# uLipo.net
KiCad netlist of a schematic drawn in EAGLE
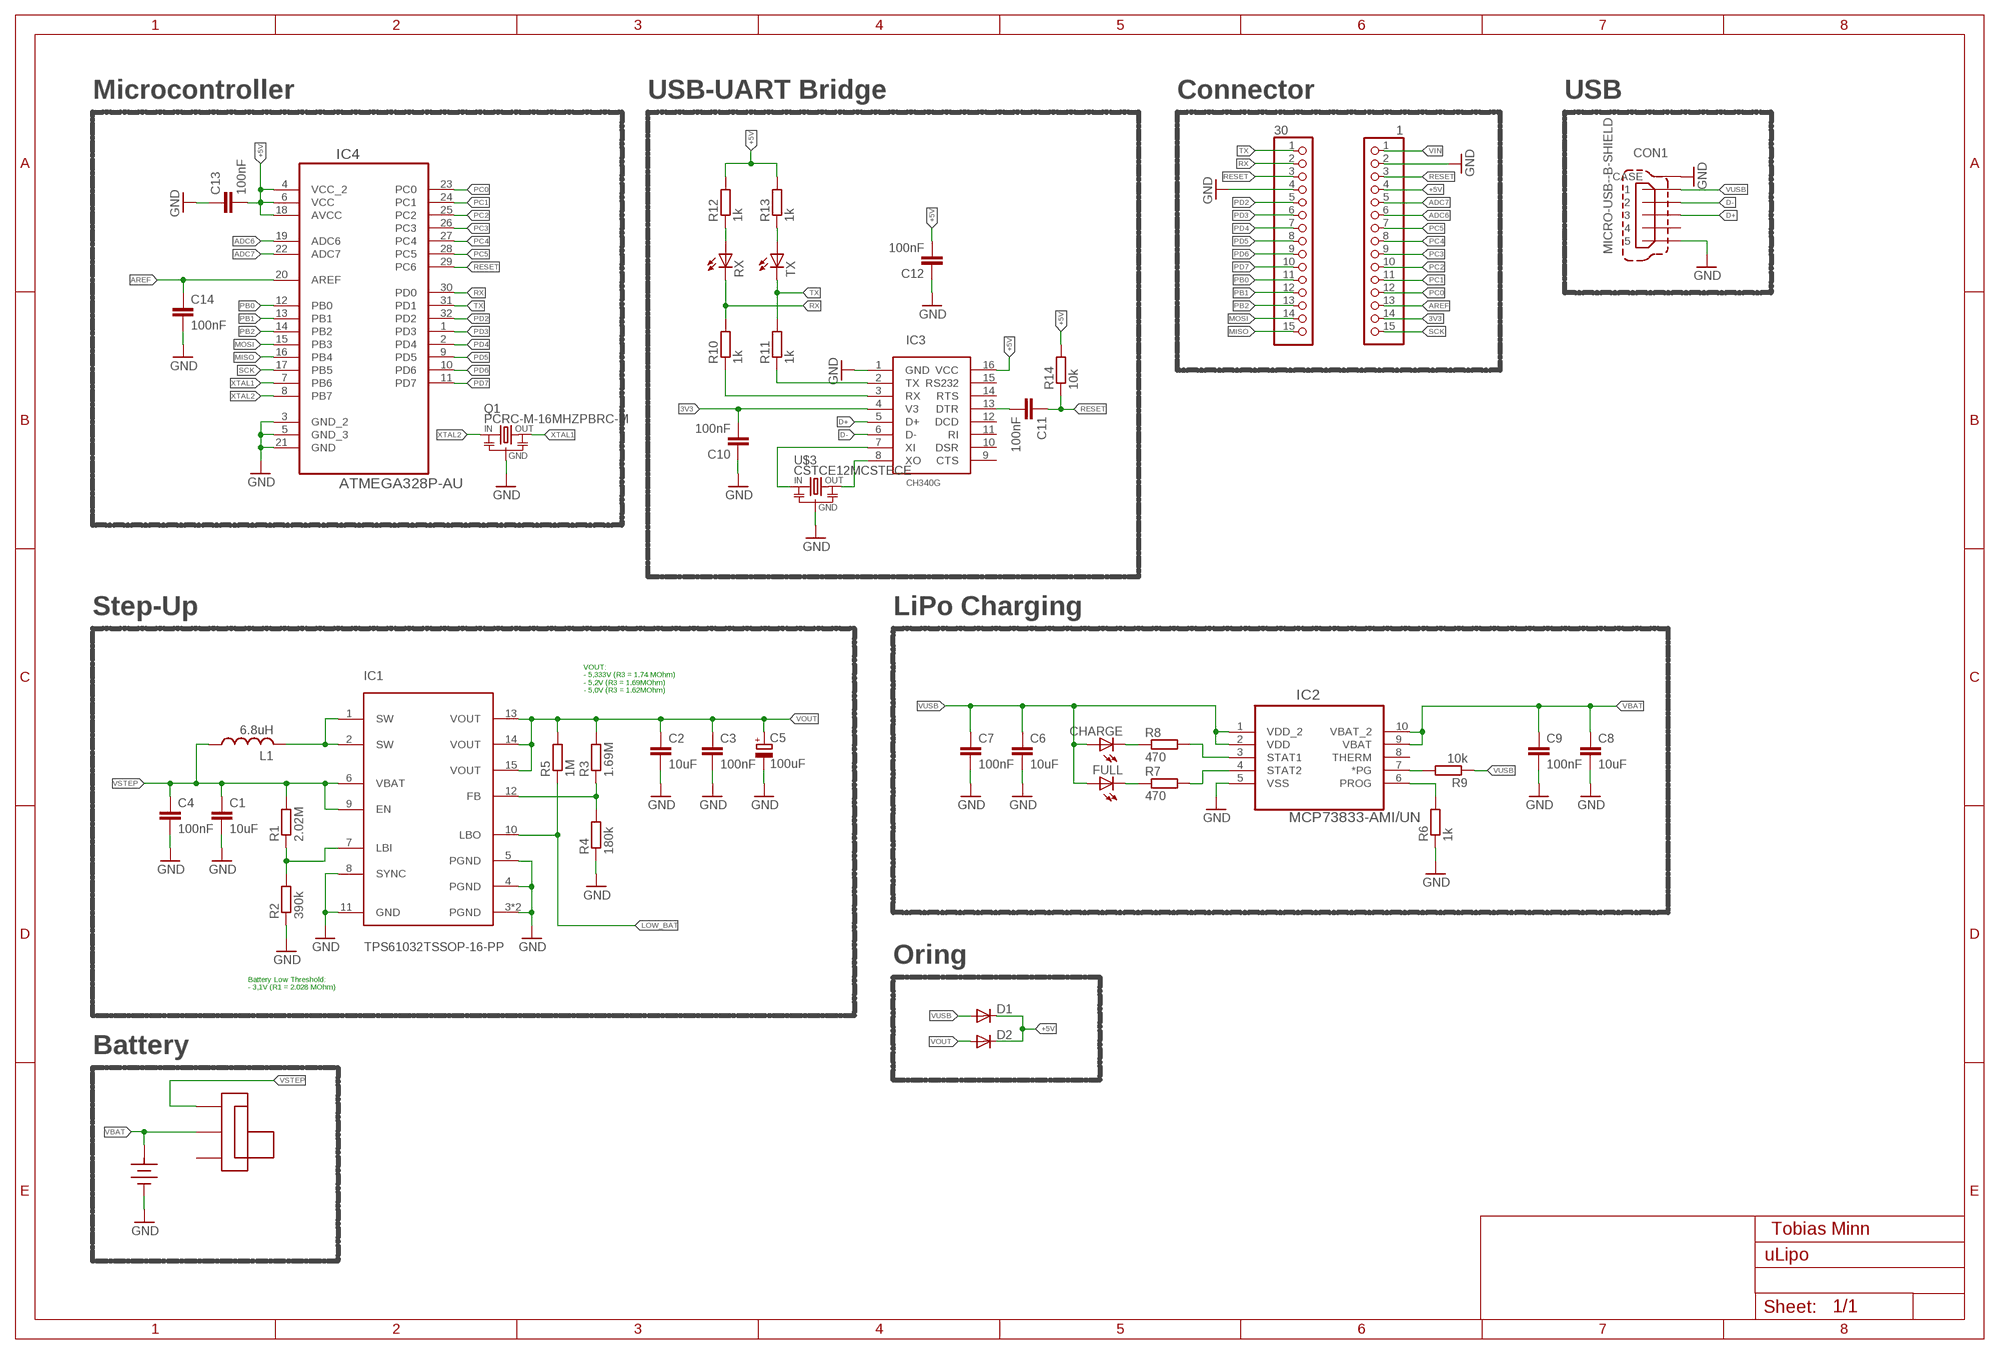
[diagram p0: schematic, sheet 1]

(export (version "E")
  (design (tool "Eeschema 10.0.6"))
  (components
    (comp (ref "1")
      (value "PINHD-1X15/OCT/BIG")
      (footprint "eagle-import:1X15_OCT_BIG")
      (libsource (lib "eagle-import") (part "PINHD-1X15/OCT/BIG"))
    )
    (comp (ref "30")
      (value "PINHD-1X15/OCT/BIG")
      (footprint "eagle-import:1X15_OCT_BIG")
      (libsource (lib "eagle-import") (part "PINHD-1X15/OCT/BIG"))
    )
    (comp (ref "BAT")
      (value "18650BATTERY")
      (footprint "eagle-import:18650BATTERY")
      (libsource (lib "eagle-import") (part "18650BATTERY"))
    )
    (comp (ref "C1")
      (value "10uF")
      (footprint "eagle-import:C0603K")
      (libsource (lib "eagle-import") (part "C-EUC0603K"))
    )
    (comp (ref "C2")
      (value "10uF")
      (footprint "eagle-import:C0603K")
      (libsource (lib "eagle-import") (part "C-EUC0603K"))
    )
    (comp (ref "C3")
      (value "100nF")
      (footprint "eagle-import:C0603K")
      (libsource (lib "eagle-import") (part "C-EUC0603K"))
    )
    (comp (ref "C4")
      (value "100nF")
      (footprint "eagle-import:C0603K")
      (libsource (lib "eagle-import") (part "C-EUC0603K"))
    )
    (comp (ref "C5")
      (value "100uF")
      (footprint "eagle-import:CT3528")
      (libsource (lib "eagle-import") (part "CPOL-EUCT3528"))
    )
    (comp (ref "C6")
      (value "10uF")
      (footprint "eagle-import:C0603K")
      (libsource (lib "eagle-import") (part "C-EUC0603K"))
    )
    (comp (ref "C7")
      (value "100nF")
      (footprint "eagle-import:C0603K")
      (libsource (lib "eagle-import") (part "C-EUC0603K"))
    )
    (comp (ref "C8")
      (value "10uF")
      (footprint "eagle-import:C0603K")
      (libsource (lib "eagle-import") (part "C-EUC0603K"))
    )
    (comp (ref "C9")
      (value "100nF")
      (footprint "eagle-import:C0603K")
      (libsource (lib "eagle-import") (part "C-EUC0603K"))
    )
    (comp (ref "C10")
      (value "100nF")
      (footprint "eagle-import:C0603K")
      (libsource (lib "eagle-import") (part "C-EUC0603K"))
    )
    (comp (ref "C11")
      (value "100nF")
      (footprint "eagle-import:C0603K")
      (libsource (lib "eagle-import") (part "C-EUC0603K"))
    )
    (comp (ref "C12")
      (value "100nF")
      (footprint "eagle-import:C0603K")
      (libsource (lib "eagle-import") (part "C-EUC0603K"))
    )
    (comp (ref "C13")
      (value "100nF")
      (footprint "eagle-import:C0603K")
      (libsource (lib "eagle-import") (part "C-EUC0603K"))
    )
    (comp (ref "C14")
      (value "100nF")
      (footprint "eagle-import:C0603K")
      (libsource (lib "eagle-import") (part "C-EUC0603K"))
    )
    (comp (ref "CHARGE")
      (value "LEDSML0603")
      (footprint "eagle-import:SML0603")
      (libsource (lib "eagle-import") (part "LEDSML0603"))
    )
    (comp (ref "CON1")
      (value "MICRO-USB--B-SHIELD")
      (footprint "eagle-import:MOLEX_47346-0001")
      (libsource (lib "eagle-import") (part "MICRO-USB--B-SHIELD"))
    )
    (comp (ref "D1")
      (value "DIODE-SOD123")
      (footprint "eagle-import:SOD123")
      (libsource (lib "eagle-import") (part "DIODE-SOD123"))
    )
    (comp (ref "D2")
      (value "DIODE-SOD123")
      (footprint "eagle-import:SOD123")
      (libsource (lib "eagle-import") (part "DIODE-SOD123"))
    )
    (comp (ref "FULL")
      (value "LEDSML0603")
      (footprint "eagle-import:SML0603")
      (libsource (lib "eagle-import") (part "LEDSML0603"))
    )
    (comp (ref "IC1")
      (value "TPS61032TSSOP-16-PP")
      (footprint "eagle-import:TSSOP-16-PP")
      (libsource (lib "eagle-import") (part "TPS61032TSSOP-16-PP"))
    )
    (comp (ref "IC2")
      (value "MCP73833-AMI/UN")
      (footprint "eagle-import:SOP50P490X110-10N")
      (libsource (lib "eagle-import") (part "MCP73833-AMI/UN"))
    )
    (comp (ref "IC3")
      (value "CH340G")
      (footprint "eagle-import:SOIC16")
      (libsource (lib "eagle-import") (part "CH340G"))
    )
    (comp (ref "IC4")
      (value "ATMEGA328P-AU")
      (footprint "eagle-import:QFP80P900X900X120-32N")
      (libsource (lib "eagle-import") (part "ATMEGA328P-AU"))
    )
    (comp (ref "L1")
      (value "6.8uH")
      (footprint "eagle-import:MGV0603")
      (libsource (lib "eagle-import") (part "L-USMGV0603"))
    )
    (comp (ref "Q1")
      (value "PCRC-M-16MHZPBRC-M")
      (footprint "eagle-import:PBRC-M")
      (libsource (lib "eagle-import") (part "PCRC-M-16MHZPBRC-M"))
    )
    (comp (ref "R1")
      (value "2.02M")
      (footprint "eagle-import:R0603")
      (libsource (lib "eagle-import") (part "R-EU_R0603"))
    )
    (comp (ref "R2")
      (value "390k")
      (footprint "eagle-import:R0603")
      (libsource (lib "eagle-import") (part "R-EU_R0603"))
    )
    (comp (ref "R3")
      (value "1.69M")
      (footprint "eagle-import:R0603")
      (libsource (lib "eagle-import") (part "R-EU_R0603"))
    )
    (comp (ref "R4")
      (value "180k")
      (footprint "eagle-import:R0603")
      (libsource (lib "eagle-import") (part "R-EU_R0603"))
    )
    (comp (ref "R5")
      (value "1M")
      (footprint "eagle-import:R0603")
      (libsource (lib "eagle-import") (part "R-EU_R0603"))
    )
    (comp (ref "R6")
      (value "1k")
      (footprint "eagle-import:R0603")
      (libsource (lib "eagle-import") (part "R-EU_R0603"))
    )
    (comp (ref "R7")
      (value "470")
      (footprint "eagle-import:R0603")
      (libsource (lib "eagle-import") (part "R-EU_R0603"))
    )
    (comp (ref "R8")
      (value "470")
      (footprint "eagle-import:R0603")
      (libsource (lib "eagle-import") (part "R-EU_R0603"))
    )
    (comp (ref "R9")
      (value "10k")
      (footprint "eagle-import:R0603")
      (libsource (lib "eagle-import") (part "R-EU_R0603"))
    )
    (comp (ref "R10")
      (value "1k")
      (footprint "eagle-import:R0603")
      (libsource (lib "eagle-import") (part "R-EU_R0603"))
    )
    (comp (ref "R11")
      (value "1k")
      (footprint "eagle-import:R0603")
      (libsource (lib "eagle-import") (part "R-EU_R0603"))
    )
    (comp (ref "R12")
      (value "1k")
      (footprint "eagle-import:R0603")
      (libsource (lib "eagle-import") (part "R-EU_R0603"))
    )
    (comp (ref "R13")
      (value "1k")
      (footprint "eagle-import:R0603")
      (libsource (lib "eagle-import") (part "R-EU_R0603"))
    )
    (comp (ref "R14")
      (value "10k")
      (footprint "eagle-import:R0603")
      (libsource (lib "eagle-import") (part "R-EU_R0603"))
    )
    (comp (ref "RX")
      (value "LEDCHIP-LED0603")
      (footprint "eagle-import:CHIP-LED0603")
      (libsource (lib "eagle-import") (part "LEDCHIP-LED0603"))
    )
    (comp (ref "TX")
      (value "LEDCHIP-LED0603")
      (footprint "eagle-import:CHIP-LED0603")
      (libsource (lib "eagle-import") (part "LEDCHIP-LED0603"))
    )
    (comp (ref "U$2")
      (value "SWITCH")
      (footprint "eagle-import:SWITCH")
      (libsource (lib "eagle-import") (part "SWITCH"))
    )
    (comp (ref "U$3")
      (value "CSTCE12MCSTECE")
      (footprint "eagle-import:CSTCE12M")
      (libsource (lib "eagle-import") (part "CSTCE12MCSTECE"))
    )
  )
  (nets
    (net (code "1") (name "+5V") (class "Default")
      (node (ref "1") (pin "4") (pinfunction "4_4") (pintype "passive"))
      (node (ref "C12") (pin "2") (pinfunction "2_2") (pintype "passive"))
      (node (ref "C13") (pin "2") (pinfunction "2_2") (pintype "passive"))
      (node (ref "D1") (pin "C") (pinfunction "C_C") (pintype "passive"))
      (node (ref "D2") (pin "C") (pinfunction "C_C") (pintype "passive"))
      (node (ref "IC3") (pin "16") (pinfunction "VCC_16") (pintype "bidirectional"))
      (node (ref "IC4") (pin "18") (pinfunction "AVCC_18") (pintype "power_in"))
      (node (ref "IC4") (pin "4") (pinfunction "VCC_2_4") (pintype "power_in"))
      (node (ref "IC4") (pin "6") (pinfunction "VCC_6") (pintype "power_in"))
      (node (ref "R12") (pin "2") (pinfunction "2_2") (pintype "passive"))
      (node (ref "R13") (pin "2") (pinfunction "2_2") (pintype "passive"))
      (node (ref "R14") (pin "2") (pinfunction "2_2") (pintype "passive"))
    )
    (net (code "2") (name "3V3") (class "Default")
      (node (ref "1") (pin "14") (pinfunction "14_14") (pintype "passive"))
      (node (ref "C10") (pin "2") (pinfunction "2_2") (pintype "passive"))
      (node (ref "IC3") (pin "4") (pinfunction "V3_4") (pintype "bidirectional"))
    )
    (net (code "3") (name "ADC6") (class "Default")
      (node (ref "1") (pin "6") (pinfunction "6_6") (pintype "passive"))
      (node (ref "IC4") (pin "19") (pinfunction "ADC6_19") (pintype "input"))
    )
    (net (code "4") (name "ADC7") (class "Default")
      (node (ref "1") (pin "5") (pinfunction "5_5") (pintype "passive"))
      (node (ref "IC4") (pin "22") (pinfunction "ADC7_22") (pintype "input"))
    )
    (net (code "5") (name "AREF") (class "Default")
      (node (ref "1") (pin "13") (pinfunction "13_13") (pintype "passive"))
      (node (ref "C14") (pin "1") (pinfunction "1_1") (pintype "passive"))
      (node (ref "IC4") (pin "20") (pinfunction "AREF_20") (pintype "input"))
    )
    (net (code "6") (name "D+") (class "Default")
      (node (ref "CON1") (pin "3") (pinfunction "3_3") (pintype "passive"))
      (node (ref "IC3") (pin "5") (pinfunction "D+_5") (pintype "bidirectional"))
    )
    (net (code "7") (name "D-") (class "Default")
      (node (ref "CON1") (pin "2") (pinfunction "2_2") (pintype "passive"))
      (node (ref "IC3") (pin "6") (pinfunction "D-_6") (pintype "bidirectional"))
    )
    (net (code "8") (name "GND") (class "Default")
      (node (ref "1") (pin "2") (pinfunction "2_2") (pintype "passive"))
      (node (ref "30") (pin "4") (pinfunction "4_4") (pintype "passive"))
      (node (ref "BAT") (pin "P$2") (pinfunction "P2_P$2") (pintype "bidirectional"))
      (node (ref "C1") (pin "2") (pinfunction "2_2") (pintype "passive"))
      (node (ref "C10") (pin "1") (pinfunction "1_1") (pintype "passive"))
      (node (ref "C12") (pin "1") (pinfunction "1_1") (pintype "passive"))
      (node (ref "C13") (pin "1") (pinfunction "1_1") (pintype "passive"))
      (node (ref "C14") (pin "2") (pinfunction "2_2") (pintype "passive"))
      (node (ref "C2") (pin "2") (pinfunction "2_2") (pintype "passive"))
      (node (ref "C3") (pin "2") (pinfunction "2_2") (pintype "passive"))
      (node (ref "C4") (pin "2") (pinfunction "2_2") (pintype "passive"))
      (node (ref "C5") (pin "-") (pinfunction "-_-") (pintype "passive"))
      (node (ref "C6") (pin "2") (pinfunction "2_2") (pintype "passive"))
      (node (ref "C7") (pin "2") (pinfunction "2_2") (pintype "passive"))
      (node (ref "C8") (pin "2") (pinfunction "2_2") (pintype "passive"))
      (node (ref "C9") (pin "2") (pinfunction "2_2") (pintype "passive"))
      (node (ref "CON1") (pin "5") (pinfunction "5_5") (pintype "passive"))
      (node (ref "CON1") (pin "M1") (pinfunction "CASE_M1") (pintype "bidirectional"))
      (node (ref "CON1") (pin "M2") (pinfunction "CASE_M2") (pintype "bidirectional"))
      (node (ref "CON1") (pin "M3") (pinfunction "CASE_M3") (pintype "bidirectional"))
      (node (ref "CON1") (pin "M4") (pinfunction "CASE_M4") (pintype "bidirectional"))
      (node (ref "CON1") (pin "M5") (pinfunction "CASE_M5") (pintype "bidirectional"))
      (node (ref "CON1") (pin "M6") (pinfunction "CASE_M6") (pintype "bidirectional"))
      (node (ref "IC1") (pin "11") (pinfunction "GND_11") (pintype "bidirectional"))
      (node (ref "IC1") (pin "17") (pinfunction "PGND_17") (pintype "bidirectional"))
      (node (ref "IC1") (pin "3") (pinfunction "PGND_3") (pintype "bidirectional"))
      (node (ref "IC1") (pin "4") (pinfunction "PGND_4") (pintype "bidirectional"))
      (node (ref "IC1") (pin "5") (pinfunction "PGND_5") (pintype "bidirectional"))
      (node (ref "IC1") (pin "8") (pinfunction "SYNC_8") (pintype "bidirectional"))
      (node (ref "IC2") (pin "5") (pinfunction "VSS_5") (pintype "passive"))
      (node (ref "IC3") (pin "1") (pinfunction "GND_1") (pintype "bidirectional"))
      (node (ref "IC4") (pin "21") (pinfunction "GND_21") (pintype "passive"))
      (node (ref "IC4") (pin "3") (pinfunction "GND_2_3") (pintype "passive"))
      (node (ref "IC4") (pin "5") (pinfunction "GND_3_5") (pintype "passive"))
      (node (ref "Q1") (pin "2") (pinfunction "GND_2") (pintype "bidirectional"))
      (node (ref "R2") (pin "1") (pinfunction "1_1") (pintype "passive"))
      (node (ref "R4") (pin "1") (pinfunction "1_1") (pintype "passive"))
      (node (ref "R6") (pin "1") (pinfunction "1_1") (pintype "passive"))
      (node (ref "U$3") (pin "2") (pinfunction "GND_2") (pintype "bidirectional"))
    )
    (net (code "9") (name "LOW_BAT") (class "Default")
      (node (ref "IC1") (pin "10") (pinfunction "LBO_10") (pintype "bidirectional"))
      (node (ref "R5") (pin "1") (pinfunction "1_1") (pintype "passive"))
    )
    (net (code "10") (name "MISO") (class "Default")
      (node (ref "30") (pin "15") (pinfunction "15_15") (pintype "passive"))
      (node (ref "IC4") (pin "16") (pinfunction "PB4_16") (pintype "bidirectional"))
    )
    (net (code "11") (name "MOSI") (class "Default")
      (node (ref "30") (pin "14") (pinfunction "14_14") (pintype "passive"))
      (node (ref "IC4") (pin "15") (pinfunction "PB3_15") (pintype "bidirectional"))
    )
    (net (code "12") (name "Net-(CHARGE-PadC)") (class "Default")
      (node (ref "CHARGE") (pin "C") (pinfunction "C_C") (pintype "passive"))
      (node (ref "R8") (pin "1") (pinfunction "1_1") (pintype "passive"))
    )
    (net (code "13") (name "Net-(FULL-PadC)") (class "Default")
      (node (ref "FULL") (pin "C") (pinfunction "C_C") (pintype "passive"))
      (node (ref "R7") (pin "1") (pinfunction "1_1") (pintype "passive"))
    )
    (net (code "14") (name "Net-(IC1-FB)") (class "Default")
      (node (ref "IC1") (pin "12") (pinfunction "FB_12") (pintype "bidirectional"))
      (node (ref "R3") (pin "1") (pinfunction "1_1") (pintype "passive"))
      (node (ref "R4") (pin "2") (pinfunction "2_2") (pintype "passive"))
    )
    (net (code "15") (name "Net-(IC1-LBI)") (class "Default")
      (node (ref "IC1") (pin "7") (pinfunction "LBI_7") (pintype "bidirectional"))
      (node (ref "R1") (pin "1") (pinfunction "1_1") (pintype "passive"))
      (node (ref "R2") (pin "2") (pinfunction "2_2") (pintype "passive"))
    )
    (net (code "16") (name "Net-(IC2-*PG)") (class "Default")
      (node (ref "IC2") (pin "7") (pinfunction "*PG_7") (pintype "input"))
      (node (ref "R9") (pin "2") (pinfunction "2_2") (pintype "passive"))
    )
    (net (code "17") (name "Net-(IC2-PROG)") (class "Default")
      (node (ref "IC2") (pin "6") (pinfunction "PROG_6") (pintype "input"))
      (node (ref "R6") (pin "2") (pinfunction "2_2") (pintype "passive"))
    )
    (net (code "18") (name "Net-(IC2-STAT1)") (class "Default")
      (node (ref "IC2") (pin "3") (pinfunction "STAT1_3") (pintype "input"))
      (node (ref "R8") (pin "2") (pinfunction "2_2") (pintype "passive"))
    )
    (net (code "19") (name "Net-(IC2-STAT2)") (class "Default")
      (node (ref "IC2") (pin "4") (pinfunction "STAT2_4") (pintype "input"))
      (node (ref "R7") (pin "2") (pinfunction "2_2") (pintype "passive"))
    )
    (net (code "20") (name "Net-(IC3-DTR)") (class "Default")
      (node (ref "C11") (pin "2") (pinfunction "2_2") (pintype "passive"))
      (node (ref "IC3") (pin "13") (pinfunction "DTR_13") (pintype "bidirectional"))
    )
    (net (code "21") (name "Net-(IC3-RX)") (class "Default")
      (node (ref "IC3") (pin "3") (pinfunction "RX_3") (pintype "bidirectional"))
      (node (ref "R10") (pin "1") (pinfunction "1_1") (pintype "passive"))
    )
    (net (code "22") (name "Net-(IC3-TX)") (class "Default")
      (node (ref "IC3") (pin "2") (pinfunction "TX_2") (pintype "bidirectional"))
      (node (ref "R11") (pin "1") (pinfunction "1_1") (pintype "passive"))
    )
    (net (code "23") (name "Net-(IC3-XI)") (class "Default")
      (node (ref "IC3") (pin "7") (pinfunction "XI_7") (pintype "bidirectional"))
      (node (ref "U$3") (pin "1") (pinfunction "IN_1") (pintype "bidirectional"))
    )
    (net (code "24") (name "Net-(IC3-XO)") (class "Default")
      (node (ref "IC3") (pin "8") (pinfunction "XO_8") (pintype "bidirectional"))
      (node (ref "U$3") (pin "3") (pinfunction "OUT_3") (pintype "bidirectional"))
    )
    (net (code "25") (name "Net-(L1-2)") (class "Default")
      (node (ref "IC1") (pin "1") (pinfunction "SW_1") (pintype "bidirectional"))
      (node (ref "IC1") (pin "2") (pinfunction "SW_2") (pintype "bidirectional"))
      (node (ref "L1") (pin "P$2") (pinfunction "2_P$2") (pintype "passive"))
    )
    (net (code "26") (name "Net-(R12-Pad1)") (class "Default")
      (node (ref "R12") (pin "1") (pinfunction "1_1") (pintype "passive"))
      (node (ref "RX") (pin "A") (pinfunction "A_A") (pintype "passive"))
    )
    (net (code "27") (name "Net-(R13-Pad1)") (class "Default")
      (node (ref "R13") (pin "1") (pinfunction "1_1") (pintype "passive"))
      (node (ref "TX") (pin "A") (pinfunction "A_A") (pintype "passive"))
    )
    (net (code "28") (name "PB0") (class "Default")
      (node (ref "30") (pin "11") (pinfunction "11_11") (pintype "passive"))
      (node (ref "IC4") (pin "12") (pinfunction "PB0_12") (pintype "bidirectional"))
    )
    (net (code "29") (name "PB1") (class "Default")
      (node (ref "30") (pin "12") (pinfunction "12_12") (pintype "passive"))
      (node (ref "IC4") (pin "13") (pinfunction "PB1_13") (pintype "bidirectional"))
    )
    (net (code "30") (name "PB2") (class "Default")
      (node (ref "30") (pin "13") (pinfunction "13_13") (pintype "passive"))
      (node (ref "IC4") (pin "14") (pinfunction "PB2_14") (pintype "bidirectional"))
    )
    (net (code "31") (name "PC0") (class "Default")
      (node (ref "1") (pin "12") (pinfunction "12_12") (pintype "passive"))
      (node (ref "IC4") (pin "23") (pinfunction "PC0_23") (pintype "bidirectional"))
    )
    (net (code "32") (name "PC1") (class "Default")
      (node (ref "1") (pin "11") (pinfunction "11_11") (pintype "passive"))
      (node (ref "IC4") (pin "24") (pinfunction "PC1_24") (pintype "bidirectional"))
    )
    (net (code "33") (name "PC2") (class "Default")
      (node (ref "1") (pin "10") (pinfunction "10_10") (pintype "passive"))
      (node (ref "IC4") (pin "25") (pinfunction "PC2_25") (pintype "bidirectional"))
    )
    (net (code "34") (name "PC3") (class "Default")
      (node (ref "1") (pin "9") (pinfunction "9_9") (pintype "passive"))
      (node (ref "IC4") (pin "26") (pinfunction "PC3_26") (pintype "bidirectional"))
    )
    (net (code "35") (name "PC4") (class "Default")
      (node (ref "1") (pin "8") (pinfunction "8_8") (pintype "passive"))
      (node (ref "IC4") (pin "27") (pinfunction "PC4_27") (pintype "bidirectional"))
    )
    (net (code "36") (name "PC5") (class "Default")
      (node (ref "1") (pin "7") (pinfunction "7_7") (pintype "passive"))
      (node (ref "IC4") (pin "28") (pinfunction "PC5_28") (pintype "bidirectional"))
    )
    (net (code "37") (name "PD2") (class "Default")
      (node (ref "30") (pin "5") (pinfunction "5_5") (pintype "passive"))
      (node (ref "IC4") (pin "32") (pinfunction "PD2_32") (pintype "bidirectional"))
    )
    (net (code "38") (name "PD3") (class "Default")
      (node (ref "30") (pin "6") (pinfunction "6_6") (pintype "passive"))
      (node (ref "IC4") (pin "1") (pinfunction "PD3_1") (pintype "bidirectional"))
    )
    (net (code "39") (name "PD4") (class "Default")
      (node (ref "30") (pin "7") (pinfunction "7_7") (pintype "passive"))
      (node (ref "IC4") (pin "2") (pinfunction "PD4_2") (pintype "bidirectional"))
    )
    (net (code "40") (name "PD5") (class "Default")
      (node (ref "30") (pin "8") (pinfunction "8_8") (pintype "passive"))
      (node (ref "IC4") (pin "9") (pinfunction "PD5_9") (pintype "bidirectional"))
    )
    (net (code "41") (name "PD6") (class "Default")
      (node (ref "30") (pin "9") (pinfunction "9_9") (pintype "passive"))
      (node (ref "IC4") (pin "10") (pinfunction "PD6_10") (pintype "bidirectional"))
    )
    (net (code "42") (name "PD7") (class "Default")
      (node (ref "30") (pin "10") (pinfunction "10_10") (pintype "passive"))
      (node (ref "IC4") (pin "11") (pinfunction "PD7_11") (pintype "bidirectional"))
    )
    (net (code "43") (name "RESET") (class "Default")
      (node (ref "1") (pin "3") (pinfunction "3_3") (pintype "passive"))
      (node (ref "30") (pin "3") (pinfunction "3_3") (pintype "passive"))
      (node (ref "C11") (pin "1") (pinfunction "1_1") (pintype "passive"))
      (node (ref "IC4") (pin "29") (pinfunction "PC6_29") (pintype "bidirectional"))
      (node (ref "R14") (pin "1") (pinfunction "1_1") (pintype "passive"))
    )
    (net (code "44") (name "RX") (class "Default")
      (node (ref "30") (pin "2") (pinfunction "2_2") (pintype "passive"))
      (node (ref "IC4") (pin "30") (pinfunction "PD0_30") (pintype "bidirectional"))
      (node (ref "R10") (pin "2") (pinfunction "2_2") (pintype "passive"))
      (node (ref "RX") (pin "C") (pinfunction "C_C") (pintype "passive"))
    )
    (net (code "45") (name "SCK") (class "Default")
      (node (ref "1") (pin "15") (pinfunction "15_15") (pintype "passive"))
      (node (ref "IC4") (pin "17") (pinfunction "PB5_17") (pintype "bidirectional"))
    )
    (net (code "46") (name "TX") (class "Default")
      (node (ref "30") (pin "1") (pinfunction "1_1") (pintype "passive"))
      (node (ref "IC4") (pin "31") (pinfunction "PD1_31") (pintype "bidirectional"))
      (node (ref "R11") (pin "2") (pinfunction "2_2") (pintype "passive"))
      (node (ref "TX") (pin "C") (pinfunction "C_C") (pintype "passive"))
    )
    (net (code "47") (name "VBAT") (class "Default")
      (node (ref "BAT") (pin "P$1") (pinfunction "P1_P$1") (pintype "bidirectional"))
      (node (ref "C8") (pin "1") (pinfunction "1_1") (pintype "passive"))
      (node (ref "C9") (pin "1") (pinfunction "1_1") (pintype "passive"))
      (node (ref "IC2") (pin "10") (pinfunction "VBAT_2_10") (pintype "output"))
      (node (ref "IC2") (pin "9") (pinfunction "VBAT_9") (pintype "output"))
      (node (ref "U$2") (pin "P$1") (pinfunction "P$2_P$1") (pintype "bidirectional"))
    )
    (net (code "48") (name "VIN") (class "Default")
      (node (ref "1") (pin "1") (pinfunction "1_1") (pintype "passive"))
    )
    (net (code "49") (name "VOUT") (class "Default")
      (node (ref "C2") (pin "1") (pinfunction "1_1") (pintype "passive"))
      (node (ref "C3") (pin "1") (pinfunction "1_1") (pintype "passive"))
      (node (ref "C5") (pin "+") (pinfunction "+_+") (pintype "passive"))
      (node (ref "D2") (pin "A") (pinfunction "A_A") (pintype "passive"))
      (node (ref "IC1") (pin "13") (pinfunction "VOUT_13") (pintype "bidirectional"))
      (node (ref "IC1") (pin "14") (pinfunction "VOUT_14") (pintype "bidirectional"))
      (node (ref "IC1") (pin "15") (pinfunction "VOUT_15") (pintype "bidirectional"))
      (node (ref "R3") (pin "2") (pinfunction "2_2") (pintype "passive"))
      (node (ref "R5") (pin "2") (pinfunction "2_2") (pintype "passive"))
    )
    (net (code "50") (name "VSTEP") (class "Default")
      (node (ref "C1") (pin "1") (pinfunction "1_1") (pintype "passive"))
      (node (ref "C4") (pin "1") (pinfunction "1_1") (pintype "passive"))
      (node (ref "IC1") (pin "6") (pinfunction "VBAT_6") (pintype "bidirectional"))
      (node (ref "IC1") (pin "9") (pinfunction "EN_9") (pintype "bidirectional"))
      (node (ref "L1") (pin "P$1") (pinfunction "1_P$1") (pintype "passive"))
      (node (ref "R1") (pin "2") (pinfunction "2_2") (pintype "passive"))
      (node (ref "U$2") (pin "P$2") (pinfunction "P$1_P$2") (pintype "bidirectional"))
    )
    (net (code "51") (name "VUSB") (class "Default")
      (node (ref "C6") (pin "1") (pinfunction "1_1") (pintype "passive"))
      (node (ref "C7") (pin "1") (pinfunction "1_1") (pintype "passive"))
      (node (ref "CHARGE") (pin "A") (pinfunction "A_A") (pintype "passive"))
      (node (ref "CON1") (pin "1") (pinfunction "1_1") (pintype "passive"))
      (node (ref "D1") (pin "A") (pinfunction "A_A") (pintype "passive"))
      (node (ref "FULL") (pin "A") (pinfunction "A_A") (pintype "passive"))
      (node (ref "IC2") (pin "1") (pinfunction "VDD_2_1") (pintype "power_in"))
      (node (ref "IC2") (pin "2") (pinfunction "VDD_2") (pintype "power_in"))
      (node (ref "R9") (pin "1") (pinfunction "1_1") (pintype "passive"))
    )
    (net (code "52") (name "XTAL1") (class "Default")
      (node (ref "IC4") (pin "7") (pinfunction "PB6_7") (pintype "bidirectional"))
      (node (ref "Q1") (pin "3") (pinfunction "OUT_3") (pintype "bidirectional"))
    )
    (net (code "53") (name "XTAL2") (class "Default")
      (node (ref "IC4") (pin "8") (pinfunction "PB7_8") (pintype "bidirectional"))
      (node (ref "Q1") (pin "1") (pinfunction "IN_1") (pintype "bidirectional"))
    )
    (net (code "54") (name "unconnected-(CON1-Pad4)") (class "Default")
      (node (ref "CON1") (pin "4") (pinfunction "4_4") (pintype "passive"))
    )
    (net (code "55") (name "unconnected-(IC2-THERM-Pad8)") (class "Default")
      (node (ref "IC2") (pin "8") (pinfunction "THERM_8") (pintype "input"))
    )
    (net (code "56") (name "unconnected-(IC3-CTS-Pad9)") (class "Default")
      (node (ref "IC3") (pin "9") (pinfunction "CTS_9") (pintype "bidirectional"))
    )
    (net (code "57") (name "unconnected-(IC3-DCD-Pad12)") (class "Default")
      (node (ref "IC3") (pin "12") (pinfunction "DCD_12") (pintype "bidirectional"))
    )
    (net (code "58") (name "unconnected-(IC3-DSR-Pad10)") (class "Default")
      (node (ref "IC3") (pin "10") (pinfunction "DSR_10") (pintype "bidirectional"))
    )
    (net (code "59") (name "unconnected-(IC3-RI-Pad11)") (class "Default")
      (node (ref "IC3") (pin "11") (pinfunction "RI_11") (pintype "bidirectional"))
    )
    (net (code "60") (name "unconnected-(IC3-RS232-Pad15)") (class "Default")
      (node (ref "IC3") (pin "15") (pinfunction "RS232_15") (pintype "bidirectional"))
    )
    (net (code "61") (name "unconnected-(IC3-RTS-Pad14)") (class "Default")
      (node (ref "IC3") (pin "14") (pinfunction "RTS_14") (pintype "bidirectional"))
    )
    (net (code "62") (name "unconnected-(U$2-PadP$3)") (class "Default")
      (node (ref "U$2") (pin "P$3") (pinfunction "P$3_P$3") (pintype "bidirectional"))
    )
  )
)
